# 9235HallEffectV1_0.net
KiCad netlist of a schematic drawn in EAGLE
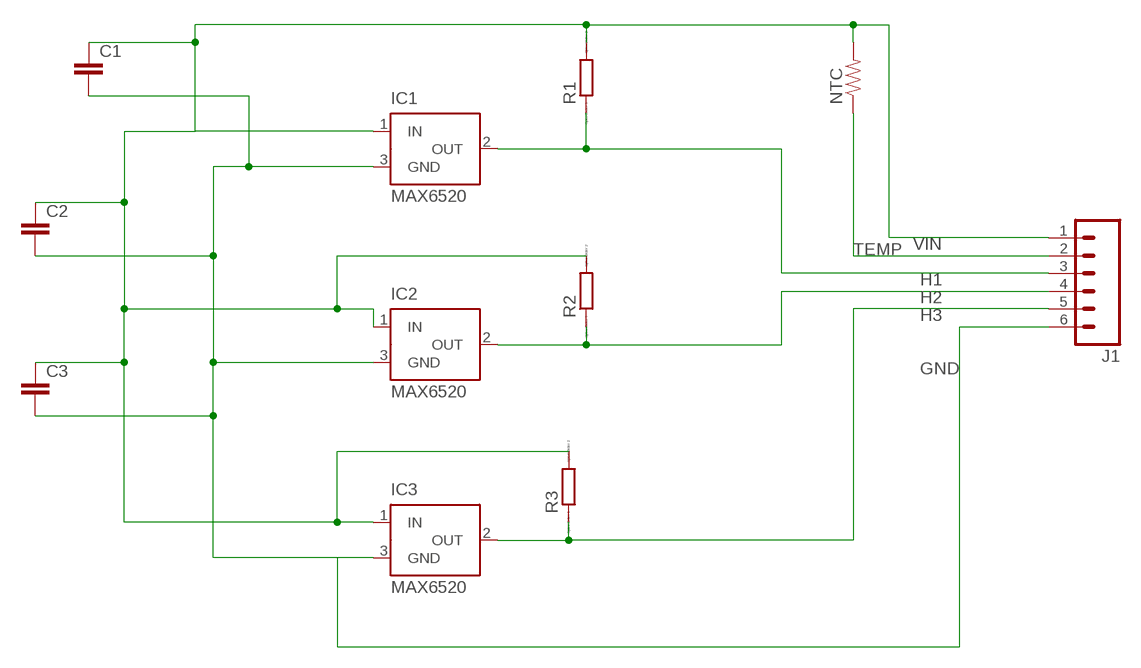
[diagram p0: schematic, sheet 1]

(export (version "E")
  (design (tool "Eeschema 10.0.6"))
  (components
    (comp (ref "C1")
      (value "C-EUC0603")
      (footprint "eagle-import:C0603")
      (libsource (lib "eagle-import") (part "C-EUC0603"))
    )
    (comp (ref "C2")
      (value "C-EUC0603")
      (footprint "eagle-import:C0603")
      (libsource (lib "eagle-import") (part "C-EUC0603"))
    )
    (comp (ref "C3")
      (value "C-EUC0603")
      (footprint "eagle-import:C0603")
      (libsource (lib "eagle-import") (part "C-EUC0603"))
    )
    (comp (ref "IC1")
      (value "MAX6520")
      (footprint "eagle-import:SOT23")
      (fields (field (name "MF") "MAXIM") (field (name "MPN") "MAX6520EUR-T"))
      (libsource (lib "eagle-import") (part "MAX6520"))
    )
    (comp (ref "IC2")
      (value "MAX6520")
      (footprint "eagle-import:SOT23")
      (fields (field (name "MF") "MAXIM") (field (name "MPN") "MAX6520EUR-T"))
      (libsource (lib "eagle-import") (part "MAX6520"))
    )
    (comp (ref "IC3")
      (value "MAX6520")
      (footprint "eagle-import:SOT23")
      (fields (field (name "MF") "MAXIM") (field (name "MPN") "MAX6520EUR-T"))
      (libsource (lib "eagle-import") (part "MAX6520"))
    )
    (comp (ref "J1")
      (value "M06SMD-1MM")
      (footprint "eagle-import:1X06-1MM")
      (libsource (lib "eagle-import") (part "M06SMD-1MM"))
    )
    (comp (ref "NTC")
      (value "RESISTOR0603-RES")
      (footprint "eagle-import:0603-RES")
      (libsource (lib "eagle-import") (part "RESISTOR0603-RES"))
    )
    (comp (ref "R1")
      (value "RR0603")
      (footprint "eagle-import:R0603")
      (libsource (lib "eagle-import") (part "RR0603"))
    )
    (comp (ref "R2")
      (value "RR0603")
      (footprint "eagle-import:R0603")
      (libsource (lib "eagle-import") (part "RR0603"))
    )
    (comp (ref "R3")
      (value "RR0603")
      (footprint "eagle-import:R0603")
      (libsource (lib "eagle-import") (part "RR0603"))
    )
  )
  (nets
    (net (code "1") (name "/GND") (class "Default")
      (node (ref "C1") (pin "2") (pinfunction "2_2") (pintype "passive"))
      (node (ref "C2") (pin "2") (pinfunction "2_2") (pintype "passive"))
      (node (ref "C3") (pin "2") (pinfunction "2_2") (pintype "passive"))
      (node (ref "IC1") (pin "3") (pinfunction "GND_3") (pintype "power_in"))
      (node (ref "IC2") (pin "3") (pinfunction "GND_3") (pintype "power_in"))
      (node (ref "IC3") (pin "3") (pinfunction "GND_3") (pintype "power_in"))
      (node (ref "J1") (pin "6") (pinfunction "6_6") (pintype "passive"))
    )
    (net (code "2") (name "/H1") (class "Default")
      (node (ref "IC1") (pin "2") (pinfunction "OUT_2") (pintype "output"))
      (node (ref "J1") (pin "3") (pinfunction "3_3") (pintype "passive"))
      (node (ref "R1") (pin "1") (pinfunction "1_1") (pintype "passive"))
    )
    (net (code "3") (name "/H2") (class "Default")
      (node (ref "IC2") (pin "2") (pinfunction "OUT_2") (pintype "output"))
      (node (ref "J1") (pin "4") (pinfunction "4_4") (pintype "passive"))
      (node (ref "R2") (pin "1") (pinfunction "1_1") (pintype "passive"))
    )
    (net (code "4") (name "/H3") (class "Default")
      (node (ref "IC3") (pin "2") (pinfunction "OUT_2") (pintype "output"))
      (node (ref "J1") (pin "5") (pinfunction "5_5") (pintype "passive"))
      (node (ref "R3") (pin "1") (pinfunction "1_1") (pintype "passive"))
    )
    (net (code "5") (name "/TEMP") (class "Default")
      (node (ref "J1") (pin "2") (pinfunction "2_2") (pintype "passive"))
      (node (ref "NTC") (pin "1") (pinfunction "1_1") (pintype "passive"))
    )
    (net (code "6") (name "/VIN") (class "Default")
      (node (ref "C1") (pin "1") (pinfunction "1_1") (pintype "passive"))
      (node (ref "C2") (pin "1") (pinfunction "1_1") (pintype "passive"))
      (node (ref "C3") (pin "1") (pinfunction "1_1") (pintype "passive"))
      (node (ref "IC1") (pin "1") (pinfunction "IN_1") (pintype "input"))
      (node (ref "IC2") (pin "1") (pinfunction "IN_1") (pintype "input"))
      (node (ref "IC3") (pin "1") (pinfunction "IN_1") (pintype "input"))
      (node (ref "J1") (pin "1") (pinfunction "1_1") (pintype "passive"))
      (node (ref "NTC") (pin "2") (pinfunction "2_2") (pintype "passive"))
      (node (ref "R1") (pin "2") (pinfunction "2_2") (pintype "passive"))
      (node (ref "R2") (pin "2") (pinfunction "2_2") (pintype "passive"))
      (node (ref "R3") (pin "2") (pinfunction "2_2") (pintype "passive"))
    )
  )
)
